# Main_Body_PCB_V4.net
KiCad netlist of a schematic drawn in EAGLE
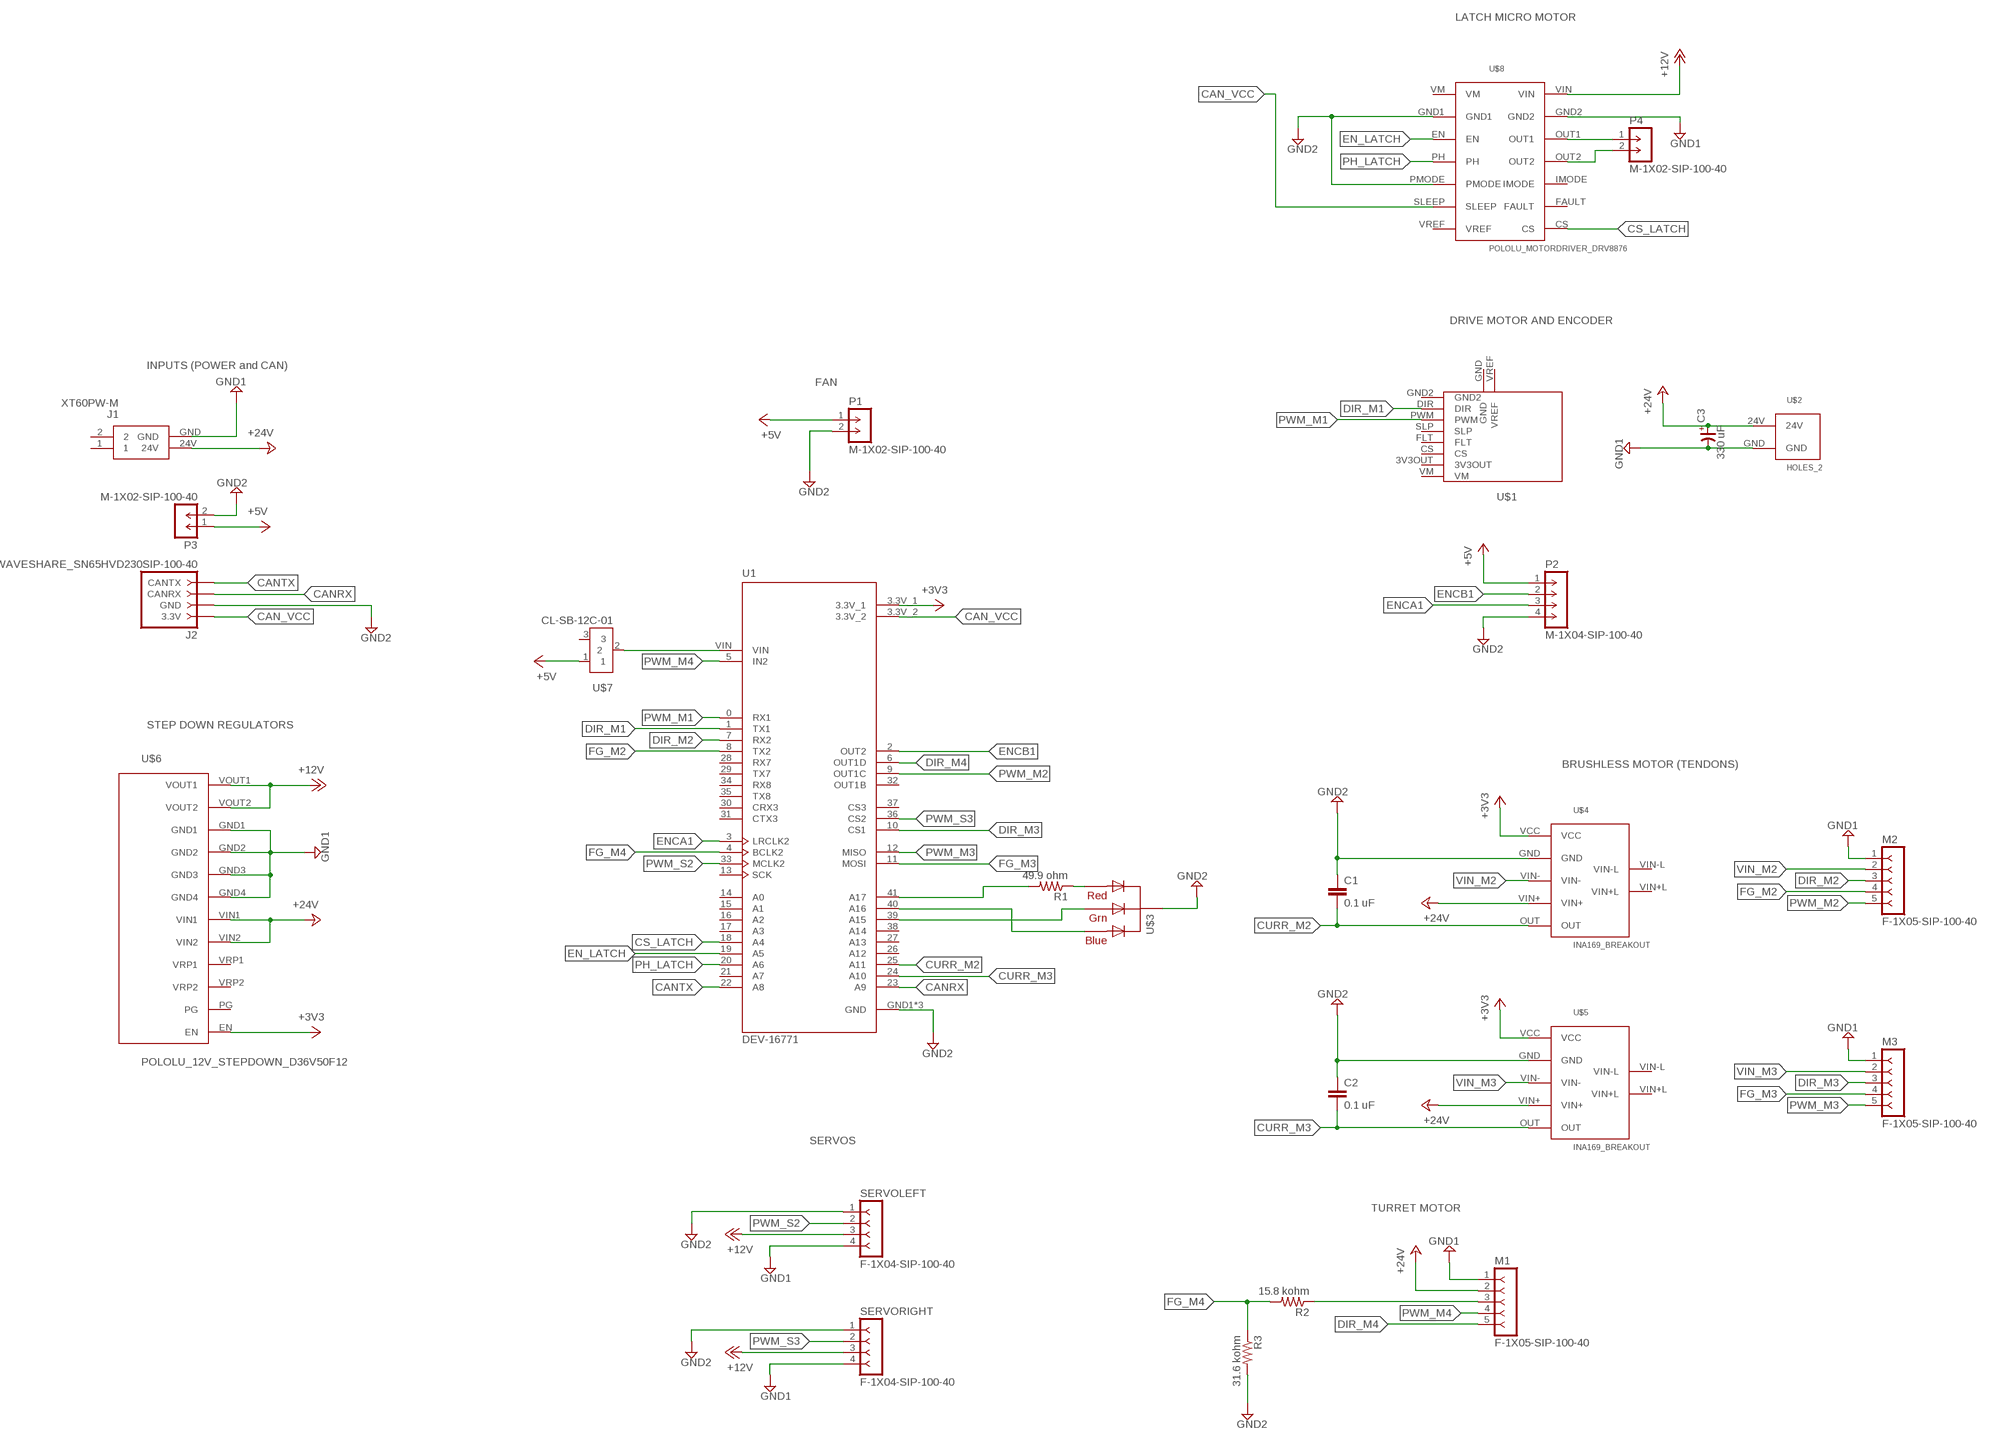
[diagram p0: schematic, sheet 1]

(export (version "E")
  (design (tool "Eeschema 10.0.6"))
  (components
    (comp (ref "C1")
      (value "0.1 uF")
      (footprint "eagle-import:C10B4")
      (libsource (lib "eagle-import") (part "C10/4"))
    )
    (comp (ref "C2")
      (value "0.1 uF")
      (footprint "eagle-import:C10B4")
      (libsource (lib "eagle-import") (part "C10/4"))
    )
    (comp (ref "C3")
      (value "330 uF")
      (footprint "eagle-import:CE-050X100")
      (libsource (lib "eagle-import") (part "CP_E-050X100"))
    )
    (comp (ref "J1")
      (value "XT60PW-M")
      (footprint "eagle-import:XT60PWM")
      (libsource (lib "eagle-import") (part "XT60PW-M"))
    )
    (comp (ref "J2")
      (value "WAVESHARE_SN65HVD230SIP-100-40")
      (footprint "eagle-import:SIP-100-04-40_PPTC041LGBN-RC")
      (libsource (lib "eagle-import") (part "WAVESHARE_SN65HVD230SIP-100-40"))
    )
    (comp (ref "M1")
      (value "F-1X05-SIP-100-40")
      (footprint "eagle-import:SIP-100-05-40")
      (libsource (lib "eagle-import") (part "F-1X05-SIP-100-40"))
    )
    (comp (ref "M2")
      (value "F-1X05-SIP-100-40")
      (footprint "eagle-import:SIP-100-05-40")
      (libsource (lib "eagle-import") (part "F-1X05-SIP-100-40"))
    )
    (comp (ref "M3")
      (value "F-1X05-SIP-100-40")
      (footprint "eagle-import:SIP-100-05-40")
      (libsource (lib "eagle-import") (part "F-1X05-SIP-100-40"))
    )
    (comp (ref "P1")
      (value "M-1X02-SIP-100-40")
      (footprint "eagle-import:SIP-100-02-40")
      (libsource (lib "eagle-import") (part "M-1X02-SIP-100-40"))
    )
    (comp (ref "P2")
      (value "M-1X04-SIP-100-40")
      (footprint "eagle-import:SIP-100-04-40")
      (libsource (lib "eagle-import") (part "M-1X04-SIP-100-40"))
    )
    (comp (ref "P3")
      (value "M-1X02-SIP-100-40")
      (footprint "eagle-import:SIP-100-02-40")
      (libsource (lib "eagle-import") (part "M-1X02-SIP-100-40"))
    )
    (comp (ref "P4")
      (value "M-1X02-SIP-100-40")
      (footprint "eagle-import:SIP-100-02-40")
      (libsource (lib "eagle-import") (part "M-1X02-SIP-100-40"))
    )
    (comp (ref "R1")
      (value "49.9 ohm")
      (footprint "eagle-import:0204_7")
      (libsource (lib "eagle-import") (part "R-US_0204/7"))
    )
    (comp (ref "R2")
      (value "15.8 kohm")
      (footprint "eagle-import:0204_7")
      (libsource (lib "eagle-import") (part "R-US_0204/7"))
    )
    (comp (ref "R3")
      (value "31.6 kohm")
      (footprint "eagle-import:0204_7")
      (libsource (lib "eagle-import") (part "R-US_0204/7"))
    )
    (comp (ref "SERVOLEFT")
      (value "F-1X04-SIP-100-40")
      (footprint "eagle-import:SIP-100-04-40")
      (libsource (lib "eagle-import") (part "F-1X04-SIP-100-40"))
    )
    (comp (ref "SERVORIGHT")
      (value "F-1X04-SIP-100-40")
      (footprint "eagle-import:SIP-100-04-40")
      (libsource (lib "eagle-import") (part "F-1X04-SIP-100-40"))
    )
    (comp (ref "U$1")
      (value "POLOLU_MOTORDRIVER_18V25_MOD")
      (footprint "eagle-import:MODULE_POLOLU_2992_2994_MOD")
      (libsource (lib "eagle-import") (part "POLOLU_MOTORDRIVER_18V25_MOD"))
    )
    (comp (ref "U$2")
      (value "HOLES_2")
      (footprint "eagle-import:HOLES_2")
      (libsource (lib "eagle-import") (part "HOLES_2"))
    )
    (comp (ref "U$3")
      (value "KINGBRIGHT_LED")
      (footprint "eagle-import:LEDWP154A4SUREQBFZGW")
      (libsource (lib "eagle-import") (part "KINGBRIGHT_LED"))
    )
    (comp (ref "U$4")
      (value "INA169_BREAKOUT")
      (footprint "eagle-import:MODULE_INA169_BREAKOUT")
      (libsource (lib "eagle-import") (part "INA169_BREAKOUT"))
    )
    (comp (ref "U$5")
      (value "INA169_BREAKOUT")
      (footprint "eagle-import:MODULE_INA169_BREAKOUT")
      (libsource (lib "eagle-import") (part "INA169_BREAKOUT"))
    )
    (comp (ref "U$6")
      (value "POLOLU_12V_STEPDOWN_D36V50F12")
      (footprint "eagle-import:MODULE_POLOLU_4093")
      (libsource (lib "eagle-import") (part "POLOLU_12V_STEPDOWN_D36V50F12"))
    )
    (comp (ref "U$7")
      (value "CL-SB-12C-01")
      (footprint "eagle-import:CL-SB-12C-01")
      (libsource (lib "eagle-import") (part "CL-SB-12C-01"))
    )
    (comp (ref "U$8")
      (value "POLOLU_MOTORDRIVER_DRV8876")
      (footprint "eagle-import:MODULE_POLOLU_4036")
      (libsource (lib "eagle-import") (part "POLOLU_MOTORDRIVER_DRV8876"))
    )
    (comp (ref "U1")
      (value "DEV-16771")
      (footprint "eagle-import:MODULE_DEV-16771")
      (fields (field (name "MF") "SparkFun Electronics"))
      (libsource (lib "eagle-import") (part "DEV-16771"))
    )
  )
  (nets
    (net (code "1") (name "+3V3") (class "Default")
      (node (ref "U$4") (pin "VCC") (pinfunction "VCC_VCC") (pintype "bidirectional"))
      (node (ref "U$5") (pin "VCC") (pinfunction "VCC_VCC") (pintype "bidirectional"))
      (node (ref "U$6") (pin "EN") (pinfunction "EN_EN") (pintype "bidirectional"))
      (node (ref "U1") (pin "3.3V_1") (pinfunction "3.3V_1_3.3V_1") (pintype "power_in"))
    )
    (net (code "2") (name "+5V") (class "Default")
      (node (ref "P1") (pin "1") (pinfunction "1_1") (pintype "passive"))
      (node (ref "P2") (pin "1") (pinfunction "1_1") (pintype "passive"))
      (node (ref "P3") (pin "1") (pinfunction "1_1") (pintype "passive"))
      (node (ref "U$7") (pin "1") (pinfunction "1_1") (pintype "bidirectional"))
    )
    (net (code "3") (name "+12V") (class "Default")
      (node (ref "SERVOLEFT") (pin "3") (pinfunction "3_3") (pintype "passive"))
      (node (ref "SERVORIGHT") (pin "3") (pinfunction "3_3") (pintype "passive"))
      (node (ref "U$6") (pin "VOUT1") (pinfunction "VOUT1_VOUT1") (pintype "bidirectional"))
      (node (ref "U$6") (pin "VOUT2") (pinfunction "VOUT2_VOUT2") (pintype "bidirectional"))
      (node (ref "U$8") (pin "VIN") (pinfunction "VIN_VIN") (pintype "bidirectional"))
    )
    (net (code "4") (name "+24V") (class "Default")
      (node (ref "C3") (pin "+") (pinfunction "+_+") (pintype "passive"))
      (node (ref "J1") (pin "24V") (pinfunction "24V_24V") (pintype "bidirectional"))
      (node (ref "M1") (pin "2") (pinfunction "2_2") (pintype "passive"))
      (node (ref "U$2") (pin "24V") (pinfunction "24V_24V") (pintype "bidirectional"))
      (node (ref "U$4") (pin "VIN+") (pinfunction "VIN+_VIN+") (pintype "bidirectional"))
      (node (ref "U$5") (pin "VIN+") (pinfunction "VIN+_VIN+") (pintype "bidirectional"))
      (node (ref "U$6") (pin "VIN1") (pinfunction "VIN1_VIN1") (pintype "bidirectional"))
      (node (ref "U$6") (pin "VIN2") (pinfunction "VIN2_VIN2") (pintype "bidirectional"))
    )
    (net (code "5") (name "CANRX") (class "Default")
      (node (ref "J2") (pin "CANRX") (pinfunction "CANRX_CANRX") (pintype "passive"))
      (node (ref "U1") (pin "23") (pinfunction "A9_23") (pintype "bidirectional"))
    )
    (net (code "6") (name "CANTX") (class "Default")
      (node (ref "J2") (pin "CANTX") (pinfunction "CANTX_CANTX") (pintype "passive"))
      (node (ref "U1") (pin "22") (pinfunction "A8_22") (pintype "bidirectional"))
    )
    (net (code "7") (name "CAN_VCC") (class "Default")
      (node (ref "J2") (pin "3.3V") (pinfunction "3.3V_3.3V") (pintype "passive"))
      (node (ref "U$8") (pin "SLEEP") (pinfunction "SLEEP_SLEEP") (pintype "bidirectional"))
      (node (ref "U1") (pin "3.3V_2") (pinfunction "3.3V_2_3.3V_2") (pintype "bidirectional"))
    )
    (net (code "8") (name "CS_LATCH") (class "Default")
      (node (ref "U$8") (pin "CS") (pinfunction "CS_CS") (pintype "bidirectional"))
      (node (ref "U1") (pin "18") (pinfunction "A4_18") (pintype "bidirectional"))
    )
    (net (code "9") (name "CURR_M2") (class "Default")
      (node (ref "C1") (pin "2") (pinfunction "2_2") (pintype "passive"))
      (node (ref "U$4") (pin "OUT") (pinfunction "OUT_OUT") (pintype "bidirectional"))
      (node (ref "U1") (pin "25") (pinfunction "A11_25") (pintype "bidirectional"))
    )
    (net (code "10") (name "CURR_M3") (class "Default")
      (node (ref "C2") (pin "2") (pinfunction "2_2") (pintype "passive"))
      (node (ref "U$5") (pin "OUT") (pinfunction "OUT_OUT") (pintype "bidirectional"))
      (node (ref "U1") (pin "24") (pinfunction "A10_24") (pintype "bidirectional"))
    )
    (net (code "11") (name "DIR_M1") (class "Default")
      (node (ref "U$1") (pin "DIR") (pinfunction "DIR_DIR") (pintype "bidirectional"))
      (node (ref "U1") (pin "1") (pinfunction "TX1_1") (pintype "bidirectional"))
    )
    (net (code "12") (name "DIR_M2") (class "Default")
      (node (ref "M2") (pin "3") (pinfunction "3_3") (pintype "passive"))
      (node (ref "U1") (pin "7") (pinfunction "RX2_7") (pintype "bidirectional"))
    )
    (net (code "13") (name "DIR_M3") (class "Default")
      (node (ref "M3") (pin "3") (pinfunction "3_3") (pintype "passive"))
      (node (ref "U1") (pin "10") (pinfunction "CS1_10") (pintype "bidirectional"))
    )
    (net (code "14") (name "DIR_M4") (class "Default")
      (node (ref "M1") (pin "5") (pinfunction "5_5") (pintype "passive"))
      (node (ref "U1") (pin "6") (pinfunction "OUT1D_6") (pintype "output"))
    )
    (net (code "15") (name "ENCA1") (class "Default")
      (node (ref "P2") (pin "3") (pinfunction "3_3") (pintype "passive"))
      (node (ref "U1") (pin "3") (pinfunction "LRCLK2_3") (pintype "bidirectional"))
    )
    (net (code "16") (name "ENCB1") (class "Default")
      (node (ref "P2") (pin "2") (pinfunction "2_2") (pintype "passive"))
      (node (ref "U1") (pin "2") (pinfunction "OUT2_2") (pintype "output"))
    )
    (net (code "17") (name "EN_LATCH") (class "Default")
      (node (ref "U$8") (pin "EN") (pinfunction "EN_EN") (pintype "bidirectional"))
      (node (ref "U1") (pin "19") (pinfunction "A5_19") (pintype "bidirectional"))
    )
    (net (code "18") (name "FG_M2") (class "Default")
      (node (ref "M2") (pin "4") (pinfunction "4_4") (pintype "passive"))
      (node (ref "U1") (pin "8") (pinfunction "TX2_8") (pintype "bidirectional"))
    )
    (net (code "19") (name "FG_M3") (class "Default")
      (node (ref "M3") (pin "4") (pinfunction "4_4") (pintype "passive"))
      (node (ref "U1") (pin "11") (pinfunction "MOSI_11") (pintype "bidirectional"))
    )
    (net (code "20") (name "FG_M4") (class "Default")
      (node (ref "R2") (pin "2") (pinfunction "2_2") (pintype "passive"))
      (node (ref "R3") (pin "1") (pinfunction "1_1") (pintype "passive"))
      (node (ref "U1") (pin "4") (pinfunction "BCLK2_4") (pintype "bidirectional"))
    )
    (net (code "21") (name "GND1") (class "Default")
      (node (ref "C3") (pin "-") (pinfunction "-_-") (pintype "passive"))
      (node (ref "J1") (pin "GND") (pinfunction "GND_GND") (pintype "bidirectional"))
      (node (ref "M1") (pin "1") (pinfunction "1_1") (pintype "passive"))
      (node (ref "M2") (pin "1") (pinfunction "1_1") (pintype "passive"))
      (node (ref "M3") (pin "1") (pinfunction "1_1") (pintype "passive"))
      (node (ref "SERVOLEFT") (pin "4") (pinfunction "4_4") (pintype "passive"))
      (node (ref "SERVORIGHT") (pin "4") (pinfunction "4_4") (pintype "passive"))
      (node (ref "U$2") (pin "GND") (pinfunction "GND_GND") (pintype "bidirectional"))
      (node (ref "U$6") (pin "GND1") (pinfunction "GND1_GND1") (pintype "bidirectional"))
      (node (ref "U$6") (pin "GND2") (pinfunction "GND2_GND2") (pintype "bidirectional"))
      (node (ref "U$6") (pin "GND3") (pinfunction "GND3_GND3") (pintype "bidirectional"))
      (node (ref "U$6") (pin "GND4") (pinfunction "GND4_GND4") (pintype "bidirectional"))
      (node (ref "U$8") (pin "GND2") (pinfunction "GND2_GND2") (pintype "bidirectional"))
    )
    (net (code "22") (name "GND2") (class "Default")
      (node (ref "C1") (pin "1") (pinfunction "1_1") (pintype "passive"))
      (node (ref "C2") (pin "1") (pinfunction "1_1") (pintype "passive"))
      (node (ref "J2") (pin "GND") (pinfunction "GND_GND") (pintype "passive"))
      (node (ref "P1") (pin "2") (pinfunction "2_2") (pintype "passive"))
      (node (ref "P2") (pin "4") (pinfunction "4_4") (pintype "passive"))
      (node (ref "P3") (pin "2") (pinfunction "2_2") (pintype "passive"))
      (node (ref "R3") (pin "2") (pinfunction "2_2") (pintype "passive"))
      (node (ref "SERVOLEFT") (pin "1") (pinfunction "1_1") (pintype "passive"))
      (node (ref "SERVORIGHT") (pin "1") (pinfunction "1_1") (pintype "passive"))
      (node (ref "U$3") (pin "GND") (pinfunction "GND_GND") (pintype "bidirectional"))
      (node (ref "U$4") (pin "GND") (pinfunction "GND_GND") (pintype "bidirectional"))
      (node (ref "U$5") (pin "GND") (pinfunction "GND_GND") (pintype "bidirectional"))
      (node (ref "U$8") (pin "GND1") (pinfunction "GND1_GND1") (pintype "bidirectional"))
      (node (ref "U$8") (pin "PMODE") (pinfunction "PMODE_PMODE") (pintype "bidirectional"))
      (node (ref "U1") (pin "GND1") (pinfunction "GND_GND1") (pintype "power_in"))
      (node (ref "U1") (pin "GND2") (pinfunction "GND_GND2") (pintype "power_in"))
      (node (ref "U1") (pin "GND3") (pinfunction "GND_GND3") (pintype "power_in"))
    )
    (net (code "23") (name "Net-(M1-Pad3)") (class "Default")
      (node (ref "M1") (pin "3") (pinfunction "3_3") (pintype "passive"))
      (node (ref "R2") (pin "1") (pinfunction "1_1") (pintype "passive"))
    )
    (net (code "24") (name "Net-(P4-Pad1)") (class "Default")
      (node (ref "P4") (pin "1") (pinfunction "1_1") (pintype "passive"))
      (node (ref "U$8") (pin "OUT1") (pinfunction "OUT1_OUT1") (pintype "bidirectional"))
    )
    (net (code "25") (name "Net-(P4-Pad2)") (class "Default")
      (node (ref "P4") (pin "2") (pinfunction "2_2") (pintype "passive"))
      (node (ref "U$8") (pin "OUT2") (pinfunction "OUT2_OUT2") (pintype "bidirectional"))
    )
    (net (code "26") (name "Net-(R1-Pad1)") (class "Default")
      (node (ref "R1") (pin "1") (pinfunction "1_1") (pintype "passive"))
      (node (ref "U$3") (pin "RED") (pinfunction "RED_RED") (pintype "bidirectional"))
    )
    (net (code "27") (name "Net-(U$3-BLUE)") (class "Default")
      (node (ref "U$3") (pin "BLU") (pinfunction "BLUE_BLU") (pintype "bidirectional"))
      (node (ref "U1") (pin "40") (pinfunction "A16_40") (pintype "bidirectional"))
    )
    (net (code "28") (name "Net-(U$3-GREEN)") (class "Default")
      (node (ref "U$3") (pin "GRN") (pinfunction "GREEN_GRN") (pintype "bidirectional"))
      (node (ref "U1") (pin "39") (pinfunction "A15_39") (pintype "bidirectional"))
    )
    (net (code "29") (name "Net-(U$7-Pad2)") (class "Default")
      (node (ref "U$7") (pin "2") (pinfunction "2_2") (pintype "bidirectional"))
      (node (ref "U1") (pin "VIN") (pinfunction "VIN_VIN") (pintype "input"))
    )
    (net (code "30") (name "Net-(U1-A17)") (class "Default")
      (node (ref "R1") (pin "2") (pinfunction "2_2") (pintype "passive"))
      (node (ref "U1") (pin "41") (pinfunction "A17_41") (pintype "bidirectional"))
    )
    (net (code "31") (name "PH_LATCH") (class "Default")
      (node (ref "U$8") (pin "PH") (pinfunction "PH_PH") (pintype "bidirectional"))
      (node (ref "U1") (pin "20") (pinfunction "A6_20") (pintype "bidirectional"))
    )
    (net (code "32") (name "PWM_M1") (class "Default")
      (node (ref "U$1") (pin "PWM") (pinfunction "PWM_PWM") (pintype "bidirectional"))
      (node (ref "U1") (pin "0") (pinfunction "RX1_0") (pintype "bidirectional"))
    )
    (net (code "33") (name "PWM_M2") (class "Default")
      (node (ref "M2") (pin "5") (pinfunction "5_5") (pintype "passive"))
      (node (ref "U1") (pin "9") (pinfunction "OUT1C_9") (pintype "output"))
    )
    (net (code "34") (name "PWM_M3") (class "Default")
      (node (ref "M3") (pin "5") (pinfunction "5_5") (pintype "passive"))
      (node (ref "U1") (pin "12") (pinfunction "MISO_12") (pintype "bidirectional"))
    )
    (net (code "35") (name "PWM_M4") (class "Default")
      (node (ref "M1") (pin "4") (pinfunction "4_4") (pintype "passive"))
      (node (ref "U1") (pin "5") (pinfunction "IN2_5") (pintype "bidirectional"))
    )
    (net (code "36") (name "PWM_S2") (class "Default")
      (node (ref "SERVOLEFT") (pin "2") (pinfunction "2_2") (pintype "passive"))
      (node (ref "U1") (pin "33") (pinfunction "MCLK2_33") (pintype "bidirectional"))
    )
    (net (code "37") (name "PWM_S3") (class "Default")
      (node (ref "SERVORIGHT") (pin "2") (pinfunction "2_2") (pintype "passive"))
      (node (ref "U1") (pin "36") (pinfunction "CS2_36") (pintype "bidirectional"))
    )
    (net (code "38") (name "VIN_M2") (class "Default")
      (node (ref "M2") (pin "2") (pinfunction "2_2") (pintype "passive"))
      (node (ref "U$4") (pin "VIN-") (pinfunction "VIN-_VIN-") (pintype "bidirectional"))
    )
    (net (code "39") (name "VIN_M3") (class "Default")
      (node (ref "M3") (pin "2") (pinfunction "2_2") (pintype "passive"))
      (node (ref "U$5") (pin "VIN-") (pinfunction "VIN-_VIN-") (pintype "bidirectional"))
    )
    (net (code "40") (name "unconnected-(J1-Pad1)") (class "Default")
      (node (ref "J1") (pin "1") (pinfunction "1_1") (pintype "bidirectional"))
    )
    (net (code "41") (name "unconnected-(J1-Pad2)") (class "Default")
      (node (ref "J1") (pin "2") (pinfunction "2_2") (pintype "bidirectional"))
    )
    (net (code "42") (name "unconnected-(U$1-Pad3V3OUT)") (class "Default")
      (node (ref "U$1") (pin "3V3OUT") (pinfunction "3V3OUT_3V3OUT") (pintype "bidirectional"))
    )
    (net (code "43") (name "unconnected-(U$1-PadCS)") (class "Default")
      (node (ref "U$1") (pin "CS") (pinfunction "CS_CS") (pintype "bidirectional"))
    )
    (net (code "44") (name "unconnected-(U$1-PadFLT)") (class "Default")
      (node (ref "U$1") (pin "FLT") (pinfunction "FLT_FLT") (pintype "bidirectional"))
    )
    (net (code "45") (name "unconnected-(U$1-PadGND)") (class "Default")
      (node (ref "U$1") (pin "GND") (pinfunction "GND_GND") (pintype "bidirectional"))
    )
    (net (code "46") (name "unconnected-(U$1-PadGND2)") (class "Default")
      (node (ref "U$1") (pin "GND2") (pinfunction "GND2_GND2") (pintype "bidirectional"))
    )
    (net (code "47") (name "unconnected-(U$1-PadSLP)") (class "Default")
      (node (ref "U$1") (pin "SLP") (pinfunction "SLP_SLP") (pintype "bidirectional"))
    )
    (net (code "48") (name "unconnected-(U$1-PadVM)") (class "Default")
      (node (ref "U$1") (pin "VM") (pinfunction "VM_VM") (pintype "bidirectional"))
    )
    (net (code "49") (name "unconnected-(U$1-PadVREF)") (class "Default")
      (node (ref "U$1") (pin "VREF") (pinfunction "VREF_VREF") (pintype "bidirectional"))
    )
    (net (code "50") (name "unconnected-(U$4-PadVIN+L)") (class "Default")
      (node (ref "U$4") (pin "VIN+L") (pinfunction "VIN+L_VIN+L") (pintype "bidirectional"))
    )
    (net (code "51") (name "unconnected-(U$4-PadVIN-L)") (class "Default")
      (node (ref "U$4") (pin "VIN-L") (pinfunction "VIN-L_VIN-L") (pintype "bidirectional"))
    )
    (net (code "52") (name "unconnected-(U$5-PadVIN+L)") (class "Default")
      (node (ref "U$5") (pin "VIN+L") (pinfunction "VIN+L_VIN+L") (pintype "bidirectional"))
    )
    (net (code "53") (name "unconnected-(U$5-PadVIN-L)") (class "Default")
      (node (ref "U$5") (pin "VIN-L") (pinfunction "VIN-L_VIN-L") (pintype "bidirectional"))
    )
    (net (code "54") (name "unconnected-(U$6-PadPG)") (class "Default")
      (node (ref "U$6") (pin "PG") (pinfunction "PG_PG") (pintype "bidirectional"))
    )
    (net (code "55") (name "unconnected-(U$6-PadVRP1)") (class "Default")
      (node (ref "U$6") (pin "VRP1") (pinfunction "VRP1_VRP1") (pintype "bidirectional"))
    )
    (net (code "56") (name "unconnected-(U$6-PadVRP2)") (class "Default")
      (node (ref "U$6") (pin "VRP2") (pinfunction "VRP2_VRP2") (pintype "bidirectional"))
    )
    (net (code "57") (name "unconnected-(U$7-Pad3)") (class "Default")
      (node (ref "U$7") (pin "3") (pinfunction "3_3") (pintype "bidirectional"))
    )
    (net (code "58") (name "unconnected-(U$8-PadFAULT)") (class "Default")
      (node (ref "U$8") (pin "FAULT") (pinfunction "FAULT_FAULT") (pintype "bidirectional"))
    )
    (net (code "59") (name "unconnected-(U$8-PadIMODE)") (class "Default")
      (node (ref "U$8") (pin "IMODE") (pinfunction "IMODE_IMODE") (pintype "bidirectional"))
    )
    (net (code "60") (name "unconnected-(U$8-PadVM)") (class "Default")
      (node (ref "U$8") (pin "VM") (pinfunction "VM_VM") (pintype "bidirectional"))
    )
    (net (code "61") (name "unconnected-(U$8-PadVREF)") (class "Default")
      (node (ref "U$8") (pin "VREF") (pinfunction "VREF_VREF") (pintype "bidirectional"))
    )
    (net (code "62") (name "unconnected-(U1-A0-Pad14)") (class "Default")
      (node (ref "U1") (pin "14") (pinfunction "A0_14") (pintype "bidirectional"))
    )
    (net (code "63") (name "unconnected-(U1-A1-Pad15)") (class "Default")
      (node (ref "U1") (pin "15") (pinfunction "A1_15") (pintype "bidirectional"))
    )
    (net (code "64") (name "unconnected-(U1-A2-Pad16)") (class "Default")
      (node (ref "U1") (pin "16") (pinfunction "A2_16") (pintype "bidirectional"))
    )
    (net (code "65") (name "unconnected-(U1-A3-Pad17)") (class "Default")
      (node (ref "U1") (pin "17") (pinfunction "A3_17") (pintype "bidirectional"))
    )
    (net (code "66") (name "unconnected-(U1-A7-Pad21)") (class "Default")
      (node (ref "U1") (pin "21") (pinfunction "A7_21") (pintype "bidirectional"))
    )
    (net (code "67") (name "unconnected-(U1-A12-Pad26)") (class "Default")
      (node (ref "U1") (pin "26") (pinfunction "A12_26") (pintype "bidirectional"))
    )
    (net (code "68") (name "unconnected-(U1-A13-Pad27)") (class "Default")
      (node (ref "U1") (pin "27") (pinfunction "A13_27") (pintype "bidirectional"))
    )
    (net (code "69") (name "unconnected-(U1-A14-Pad38)") (class "Default")
      (node (ref "U1") (pin "38") (pinfunction "A14_38") (pintype "bidirectional"))
    )
    (net (code "70") (name "unconnected-(U1-CRX3-Pad30)") (class "Default")
      (node (ref "U1") (pin "30") (pinfunction "CRX3_30") (pintype "bidirectional"))
    )
    (net (code "71") (name "unconnected-(U1-CS3-Pad37)") (class "Default")
      (node (ref "U1") (pin "37") (pinfunction "CS3_37") (pintype "bidirectional"))
    )
    (net (code "72") (name "unconnected-(U1-CTX3-Pad31)") (class "Default")
      (node (ref "U1") (pin "31") (pinfunction "CTX3_31") (pintype "bidirectional"))
    )
    (net (code "73") (name "unconnected-(U1-OUT1B-Pad32)") (class "Default")
      (node (ref "U1") (pin "32") (pinfunction "OUT1B_32") (pintype "output"))
    )
    (net (code "74") (name "unconnected-(U1-RX7-Pad28)") (class "Default")
      (node (ref "U1") (pin "28") (pinfunction "RX7_28") (pintype "bidirectional"))
    )
    (net (code "75") (name "unconnected-(U1-RX8-Pad34)") (class "Default")
      (node (ref "U1") (pin "34") (pinfunction "RX8_34") (pintype "bidirectional"))
    )
    (net (code "76") (name "unconnected-(U1-SCK-Pad13)") (class "Default")
      (node (ref "U1") (pin "13") (pinfunction "SCK_13") (pintype "bidirectional"))
    )
    (net (code "77") (name "unconnected-(U1-TX7-Pad29)") (class "Default")
      (node (ref "U1") (pin "29") (pinfunction "TX7_29") (pintype "bidirectional"))
    )
    (net (code "78") (name "unconnected-(U1-TX8-Pad35)") (class "Default")
      (node (ref "U1") (pin "35") (pinfunction "TX8_35") (pintype "bidirectional"))
    )
  )
)
